# pressure.net
KiCad netlist of a schematic drawn in EAGLE
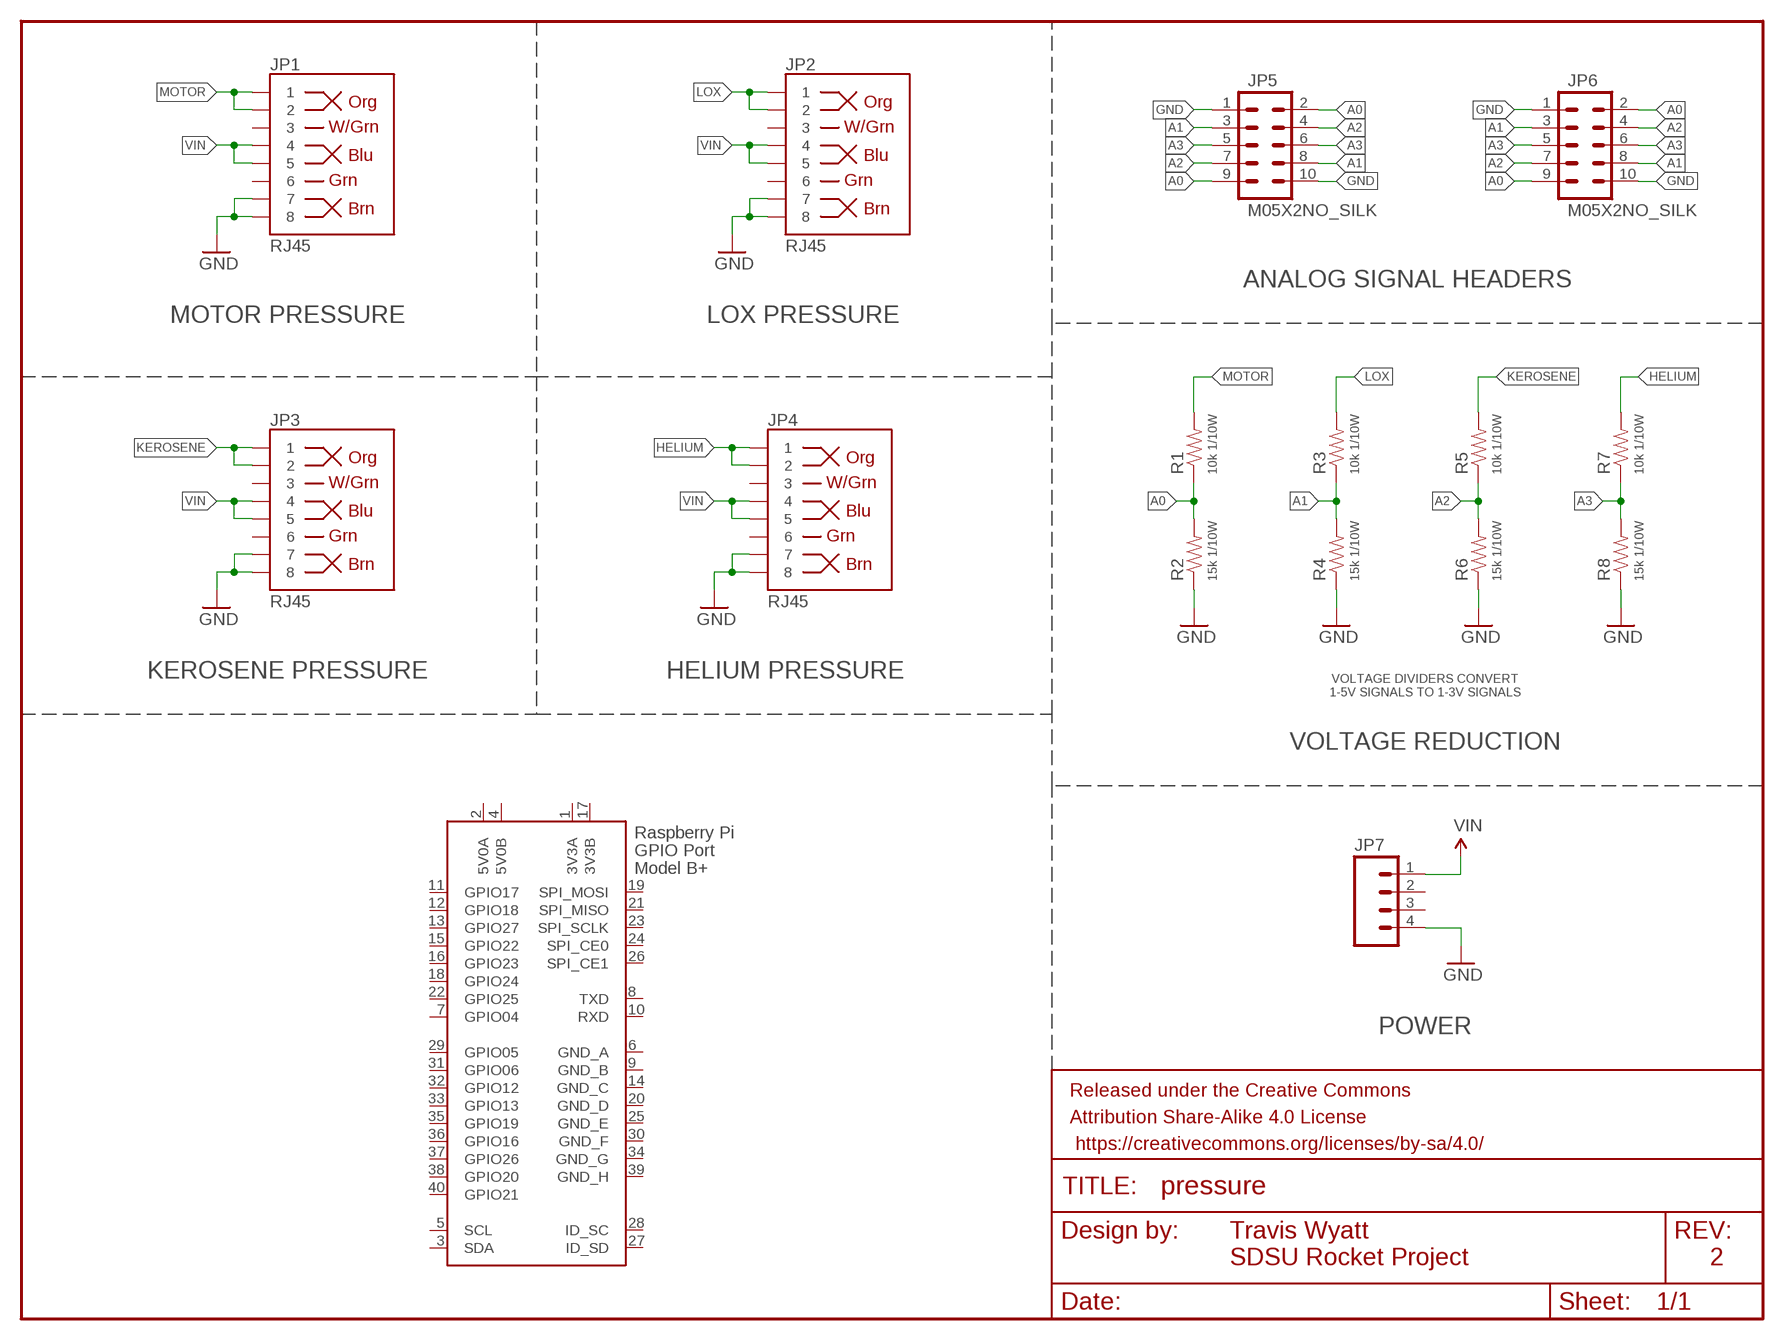
[diagram p0: schematic, sheet 1]

(export (version "E")
  (design (tool "Eeschema 10.0.6"))
  (components
    (comp (ref "FRAME1")
      (value "FRAME-LETTER")
      (footprint "eagle-import:CREATIVE_COMMONS")
      (fields (field (name "DESIGNER") "NAME"))
      (libsource (lib "eagle-import") (part "FRAME-LETTER"))
    )
    (comp (ref "JP1")
      (value "RJ45")
      (footprint "eagle-import:RJ45-8")
      (libsource (lib "eagle-import") (part "RJ45-8PTH"))
    )
    (comp (ref "JP2")
      (value "RJ45")
      (footprint "eagle-import:RJ45-8")
      (libsource (lib "eagle-import") (part "RJ45-8PTH"))
    )
    (comp (ref "JP3")
      (value "RJ45")
      (footprint "eagle-import:RJ45-8")
      (libsource (lib "eagle-import") (part "RJ45-8PTH"))
    )
    (comp (ref "JP4")
      (value "RJ45")
      (footprint "eagle-import:RJ45-8")
      (libsource (lib "eagle-import") (part "RJ45-8PTH"))
    )
    (comp (ref "JP5")
      (value "M05X2NO_SILK")
      (footprint "eagle-import:2X5_NOSILK")
      (libsource (lib "eagle-import") (part "M05X2NO_SILK"))
    )
    (comp (ref "JP6")
      (value "M05X2NO_SILK")
      (footprint "eagle-import:2X5_NOSILK")
      (libsource (lib "eagle-import") (part "M05X2NO_SILK"))
    )
    (comp (ref "JP7")
      (value "JST-4POS-2.5MM")
      (footprint "eagle-import:S4B-XH-SM4-TB")
      (libsource (lib "eagle-import") (part "JST-4POS-2.5MM"))
    )
    (comp (ref "R1")
      (value "10k 1/10W")
      (footprint "eagle-import:0603-RES")
      (libsource (lib "eagle-import") (part "RESISTOR0603-RES"))
    )
    (comp (ref "R2")
      (value "15k 1/10W")
      (footprint "eagle-import:0603-RES")
      (libsource (lib "eagle-import") (part "RESISTOR0603-RES"))
    )
    (comp (ref "R3")
      (value "10k 1/10W")
      (footprint "eagle-import:0603-RES")
      (libsource (lib "eagle-import") (part "RESISTOR0603-RES"))
    )
    (comp (ref "R4")
      (value "15k 1/10W")
      (footprint "eagle-import:0603-RES")
      (libsource (lib "eagle-import") (part "RESISTOR0603-RES"))
    )
    (comp (ref "R5")
      (value "10k 1/10W")
      (footprint "eagle-import:0603-RES")
      (libsource (lib "eagle-import") (part "RESISTOR0603-RES"))
    )
    (comp (ref "R6")
      (value "15k 1/10W")
      (footprint "eagle-import:0603-RES")
      (libsource (lib "eagle-import") (part "RESISTOR0603-RES"))
    )
    (comp (ref "R7")
      (value "10k 1/10W")
      (footprint "eagle-import:0603-RES")
      (libsource (lib "eagle-import") (part "RESISTOR0603-RES"))
    )
    (comp (ref "R8")
      (value "15k 1/10W")
      (footprint "eagle-import:0603-RES")
      (libsource (lib "eagle-import") (part "RESISTOR0603-RES"))
    )
    (comp (ref "X1")
      (value "RASPI_BOARD_B+#_H")
      (footprint "eagle-import:RASPI_BOARD_B+HAT")
      (libsource (lib "eagle-import") (part "RASPI_BOARD_B+#_H"))
    )
  )
  (nets
    (net (code "1") (name "/3V3A") (class "Default")
      (node (ref "X1") (pin "1") (pinfunction "3V3A_1") (pintype "power_in"))
    )
    (net (code "2") (name "/3V3B") (class "Default")
      (node (ref "X1") (pin "17") (pinfunction "3V3B_17") (pintype "power_in"))
    )
    (net (code "3") (name "/5V0A") (class "Default")
      (node (ref "X1") (pin "2") (pinfunction "5V0A_2") (pintype "power_in"))
    )
    (net (code "4") (name "/5V0B") (class "Default")
      (node (ref "X1") (pin "4") (pinfunction "5V0B_4") (pintype "power_in"))
    )
    (net (code "5") (name "/GND_A") (class "Default")
      (node (ref "X1") (pin "6") (pinfunction "GND_A_6") (pintype "power_in"))
    )
    (net (code "6") (name "/GND_B") (class "Default")
      (node (ref "X1") (pin "9") (pinfunction "GND_B_9") (pintype "power_in"))
    )
    (net (code "7") (name "/GND_C") (class "Default")
      (node (ref "X1") (pin "14") (pinfunction "GND_C_14") (pintype "power_in"))
    )
    (net (code "8") (name "/GND_D") (class "Default")
      (node (ref "X1") (pin "20") (pinfunction "GND_D_20") (pintype "power_in"))
    )
    (net (code "9") (name "/GND_E") (class "Default")
      (node (ref "X1") (pin "25") (pinfunction "GND_E_25") (pintype "power_in"))
    )
    (net (code "10") (name "/GND_F") (class "Default")
      (node (ref "X1") (pin "30") (pinfunction "GND_F_30") (pintype "power_in"))
    )
    (net (code "11") (name "/GND_G") (class "Default")
      (node (ref "X1") (pin "34") (pinfunction "GND_G_34") (pintype "power_in"))
    )
    (net (code "12") (name "/GND_H") (class "Default")
      (node (ref "X1") (pin "39") (pinfunction "GND_H_39") (pintype "power_in"))
    )
    (net (code "13") (name "A0") (class "Default")
      (node (ref "JP5") (pin "2") (pinfunction "2_2") (pintype "passive"))
      (node (ref "JP5") (pin "9") (pinfunction "9_9") (pintype "passive"))
      (node (ref "JP6") (pin "2") (pinfunction "2_2") (pintype "passive"))
      (node (ref "JP6") (pin "9") (pinfunction "9_9") (pintype "passive"))
      (node (ref "R1") (pin "1") (pinfunction "1_1") (pintype "passive"))
      (node (ref "R2") (pin "2") (pinfunction "2_2") (pintype "passive"))
    )
    (net (code "14") (name "A1") (class "Default")
      (node (ref "JP5") (pin "3") (pinfunction "3_3") (pintype "passive"))
      (node (ref "JP5") (pin "8") (pinfunction "8_8") (pintype "passive"))
      (node (ref "JP6") (pin "3") (pinfunction "3_3") (pintype "passive"))
      (node (ref "JP6") (pin "8") (pinfunction "8_8") (pintype "passive"))
      (node (ref "R3") (pin "1") (pinfunction "1_1") (pintype "passive"))
      (node (ref "R4") (pin "2") (pinfunction "2_2") (pintype "passive"))
    )
    (net (code "15") (name "A2") (class "Default")
      (node (ref "JP5") (pin "4") (pinfunction "4_4") (pintype "passive"))
      (node (ref "JP5") (pin "7") (pinfunction "7_7") (pintype "passive"))
      (node (ref "JP6") (pin "4") (pinfunction "4_4") (pintype "passive"))
      (node (ref "JP6") (pin "7") (pinfunction "7_7") (pintype "passive"))
      (node (ref "R5") (pin "1") (pinfunction "1_1") (pintype "passive"))
      (node (ref "R6") (pin "2") (pinfunction "2_2") (pintype "passive"))
    )
    (net (code "16") (name "A3") (class "Default")
      (node (ref "JP5") (pin "5") (pinfunction "5_5") (pintype "passive"))
      (node (ref "JP5") (pin "6") (pinfunction "6_6") (pintype "passive"))
      (node (ref "JP6") (pin "5") (pinfunction "5_5") (pintype "passive"))
      (node (ref "JP6") (pin "6") (pinfunction "6_6") (pintype "passive"))
      (node (ref "R7") (pin "1") (pinfunction "1_1") (pintype "passive"))
      (node (ref "R8") (pin "2") (pinfunction "2_2") (pintype "passive"))
    )
    (net (code "17") (name "GND") (class "Default")
      (node (ref "JP1") (pin "7") (pinfunction "7_7") (pintype "bidirectional"))
      (node (ref "JP1") (pin "8") (pinfunction "8_8") (pintype "bidirectional"))
      (node (ref "JP2") (pin "7") (pinfunction "7_7") (pintype "bidirectional"))
      (node (ref "JP2") (pin "8") (pinfunction "8_8") (pintype "bidirectional"))
      (node (ref "JP3") (pin "7") (pinfunction "7_7") (pintype "bidirectional"))
      (node (ref "JP3") (pin "8") (pinfunction "8_8") (pintype "bidirectional"))
      (node (ref "JP4") (pin "7") (pinfunction "7_7") (pintype "bidirectional"))
      (node (ref "JP4") (pin "8") (pinfunction "8_8") (pintype "bidirectional"))
      (node (ref "JP5") (pin "1") (pinfunction "1_1") (pintype "passive"))
      (node (ref "JP5") (pin "10") (pinfunction "10_10") (pintype "passive"))
      (node (ref "JP6") (pin "1") (pinfunction "1_1") (pintype "passive"))
      (node (ref "JP6") (pin "10") (pinfunction "10_10") (pintype "passive"))
      (node (ref "JP7") (pin "4") (pinfunction "4_4") (pintype "passive"))
      (node (ref "R2") (pin "1") (pinfunction "1_1") (pintype "passive"))
      (node (ref "R4") (pin "1") (pinfunction "1_1") (pintype "passive"))
      (node (ref "R6") (pin "1") (pinfunction "1_1") (pintype "passive"))
      (node (ref "R8") (pin "1") (pinfunction "1_1") (pintype "passive"))
    )
    (net (code "18") (name "HELIUM") (class "Default")
      (node (ref "JP4") (pin "1") (pinfunction "1_1") (pintype "bidirectional"))
      (node (ref "JP4") (pin "2") (pinfunction "2_2") (pintype "bidirectional"))
      (node (ref "R7") (pin "2") (pinfunction "2_2") (pintype "passive"))
    )
    (net (code "19") (name "KEROSENE") (class "Default")
      (node (ref "JP3") (pin "1") (pinfunction "1_1") (pintype "bidirectional"))
      (node (ref "JP3") (pin "2") (pinfunction "2_2") (pintype "bidirectional"))
      (node (ref "R5") (pin "2") (pinfunction "2_2") (pintype "passive"))
    )
    (net (code "20") (name "LOX") (class "Default")
      (node (ref "JP2") (pin "1") (pinfunction "1_1") (pintype "bidirectional"))
      (node (ref "JP2") (pin "2") (pinfunction "2_2") (pintype "bidirectional"))
      (node (ref "R3") (pin "2") (pinfunction "2_2") (pintype "passive"))
    )
    (net (code "21") (name "MOTOR") (class "Default")
      (node (ref "JP1") (pin "1") (pinfunction "1_1") (pintype "bidirectional"))
      (node (ref "JP1") (pin "2") (pinfunction "2_2") (pintype "bidirectional"))
      (node (ref "R1") (pin "2") (pinfunction "2_2") (pintype "passive"))
    )
    (net (code "22") (name "VIN") (class "Default")
      (node (ref "JP1") (pin "4") (pinfunction "4_4") (pintype "bidirectional"))
      (node (ref "JP1") (pin "5") (pinfunction "5_5") (pintype "bidirectional"))
      (node (ref "JP2") (pin "4") (pinfunction "4_4") (pintype "bidirectional"))
      (node (ref "JP2") (pin "5") (pinfunction "5_5") (pintype "bidirectional"))
      (node (ref "JP3") (pin "4") (pinfunction "4_4") (pintype "bidirectional"))
      (node (ref "JP3") (pin "5") (pinfunction "5_5") (pintype "bidirectional"))
      (node (ref "JP4") (pin "4") (pinfunction "4_4") (pintype "bidirectional"))
      (node (ref "JP4") (pin "5") (pinfunction "5_5") (pintype "bidirectional"))
      (node (ref "JP7") (pin "1") (pinfunction "1_1") (pintype "passive"))
    )
    (net (code "23") (name "unconnected-(JP1-Pad3)") (class "Default")
      (node (ref "JP1") (pin "3") (pinfunction "3_3") (pintype "bidirectional"))
    )
    (net (code "24") (name "unconnected-(JP1-Pad6)") (class "Default")
      (node (ref "JP1") (pin "6") (pinfunction "6_6") (pintype "bidirectional"))
    )
    (net (code "25") (name "unconnected-(JP2-Pad3)") (class "Default")
      (node (ref "JP2") (pin "3") (pinfunction "3_3") (pintype "bidirectional"))
    )
    (net (code "26") (name "unconnected-(JP2-Pad6)") (class "Default")
      (node (ref "JP2") (pin "6") (pinfunction "6_6") (pintype "bidirectional"))
    )
    (net (code "27") (name "unconnected-(JP3-Pad3)") (class "Default")
      (node (ref "JP3") (pin "3") (pinfunction "3_3") (pintype "bidirectional"))
    )
    (net (code "28") (name "unconnected-(JP3-Pad6)") (class "Default")
      (node (ref "JP3") (pin "6") (pinfunction "6_6") (pintype "bidirectional"))
    )
    (net (code "29") (name "unconnected-(JP4-Pad3)") (class "Default")
      (node (ref "JP4") (pin "3") (pinfunction "3_3") (pintype "bidirectional"))
    )
    (net (code "30") (name "unconnected-(JP4-Pad6)") (class "Default")
      (node (ref "JP4") (pin "6") (pinfunction "6_6") (pintype "bidirectional"))
    )
    (net (code "31") (name "unconnected-(JP7-Pad2)") (class "Default")
      (node (ref "JP7") (pin "2") (pinfunction "2_2") (pintype "passive"))
    )
    (net (code "32") (name "unconnected-(JP7-Pad3)") (class "Default")
      (node (ref "JP7") (pin "3") (pinfunction "3_3") (pintype "passive"))
    )
    (net (code "33") (name "unconnected-(X1-GPIO04-Pad7)") (class "Default")
      (node (ref "X1") (pin "7") (pinfunction "GPIO04_7") (pintype "bidirectional"))
    )
    (net (code "34") (name "unconnected-(X1-GPIO05-Pad29)") (class "Default")
      (node (ref "X1") (pin "29") (pinfunction "GPIO05_29") (pintype "no_connect"))
    )
    (net (code "35") (name "unconnected-(X1-GPIO06-Pad31)") (class "Default")
      (node (ref "X1") (pin "31") (pinfunction "GPIO06_31") (pintype "no_connect"))
    )
    (net (code "36") (name "unconnected-(X1-GPIO12-Pad32)") (class "Default")
      (node (ref "X1") (pin "32") (pinfunction "GPIO12_32") (pintype "no_connect"))
    )
    (net (code "37") (name "unconnected-(X1-GPIO13-Pad33)") (class "Default")
      (node (ref "X1") (pin "33") (pinfunction "GPIO13_33") (pintype "no_connect"))
    )
    (net (code "38") (name "unconnected-(X1-GPIO16-Pad36)") (class "Default")
      (node (ref "X1") (pin "36") (pinfunction "GPIO16_36") (pintype "no_connect"))
    )
    (net (code "39") (name "unconnected-(X1-GPIO17-Pad11)") (class "Default")
      (node (ref "X1") (pin "11") (pinfunction "GPIO17_11") (pintype "bidirectional"))
    )
    (net (code "40") (name "unconnected-(X1-GPIO18-Pad12)") (class "Default")
      (node (ref "X1") (pin "12") (pinfunction "GPIO18_12") (pintype "bidirectional"))
    )
    (net (code "41") (name "unconnected-(X1-GPIO19-Pad35)") (class "Default")
      (node (ref "X1") (pin "35") (pinfunction "GPIO19_35") (pintype "no_connect"))
    )
    (net (code "42") (name "unconnected-(X1-GPIO20-Pad38)") (class "Default")
      (node (ref "X1") (pin "38") (pinfunction "GPIO20_38") (pintype "no_connect"))
    )
    (net (code "43") (name "unconnected-(X1-GPIO21-Pad40)") (class "Default")
      (node (ref "X1") (pin "40") (pinfunction "GPIO21_40") (pintype "no_connect"))
    )
    (net (code "44") (name "unconnected-(X1-GPIO22-Pad15)") (class "Default")
      (node (ref "X1") (pin "15") (pinfunction "GPIO22_15") (pintype "bidirectional"))
    )
    (net (code "45") (name "unconnected-(X1-GPIO23-Pad16)") (class "Default")
      (node (ref "X1") (pin "16") (pinfunction "GPIO23_16") (pintype "bidirectional"))
    )
    (net (code "46") (name "unconnected-(X1-GPIO24-Pad18)") (class "Default")
      (node (ref "X1") (pin "18") (pinfunction "GPIO24_18") (pintype "bidirectional"))
    )
    (net (code "47") (name "unconnected-(X1-GPIO25-Pad22)") (class "Default")
      (node (ref "X1") (pin "22") (pinfunction "GPIO25_22") (pintype "bidirectional"))
    )
    (net (code "48") (name "unconnected-(X1-GPIO26-Pad37)") (class "Default")
      (node (ref "X1") (pin "37") (pinfunction "GPIO26_37") (pintype "no_connect"))
    )
    (net (code "49") (name "unconnected-(X1-GPIO27-Pad13)") (class "Default")
      (node (ref "X1") (pin "13") (pinfunction "GPIO27_13") (pintype "bidirectional"))
    )
    (net (code "50") (name "unconnected-(X1-ID_SC-Pad28)") (class "Default")
      (node (ref "X1") (pin "28") (pinfunction "ID_SC_28") (pintype "no_connect"))
    )
    (net (code "51") (name "unconnected-(X1-ID_SD-Pad27)") (class "Default")
      (node (ref "X1") (pin "27") (pinfunction "ID_SD_27") (pintype "no_connect"))
    )
    (net (code "52") (name "unconnected-(X1-RXD-Pad10)") (class "Default")
      (node (ref "X1") (pin "10") (pinfunction "RXD_10") (pintype "bidirectional"))
    )
    (net (code "53") (name "unconnected-(X1-SCL-Pad5)") (class "Default")
      (node (ref "X1") (pin "5") (pinfunction "SCL_5") (pintype "bidirectional"))
    )
    (net (code "54") (name "unconnected-(X1-SDA-Pad3)") (class "Default")
      (node (ref "X1") (pin "3") (pinfunction "SDA_3") (pintype "bidirectional"))
    )
    (net (code "55") (name "unconnected-(X1-SPI_CE0-Pad24)") (class "Default")
      (node (ref "X1") (pin "24") (pinfunction "SPI_CE0_24") (pintype "bidirectional"))
    )
    (net (code "56") (name "unconnected-(X1-SPI_CE1-Pad26)") (class "Default")
      (node (ref "X1") (pin "26") (pinfunction "SPI_CE1_26") (pintype "bidirectional"))
    )
    (net (code "57") (name "unconnected-(X1-SPI_MISO-Pad21)") (class "Default")
      (node (ref "X1") (pin "21") (pinfunction "SPI_MISO_21") (pintype "bidirectional"))
    )
    (net (code "58") (name "unconnected-(X1-SPI_MOSI-Pad19)") (class "Default")
      (node (ref "X1") (pin "19") (pinfunction "SPI_MOSI_19") (pintype "bidirectional"))
    )
    (net (code "59") (name "unconnected-(X1-SPI_SCLK-Pad23)") (class "Default")
      (node (ref "X1") (pin "23") (pinfunction "SPI_SCLK_23") (pintype "bidirectional"))
    )
    (net (code "60") (name "unconnected-(X1-TXD-Pad8)") (class "Default")
      (node (ref "X1") (pin "8") (pinfunction "TXD_8") (pintype "bidirectional"))
    )
  )
)
